# PWR.net
KiCad netlist of a schematic drawn in Altium Designer
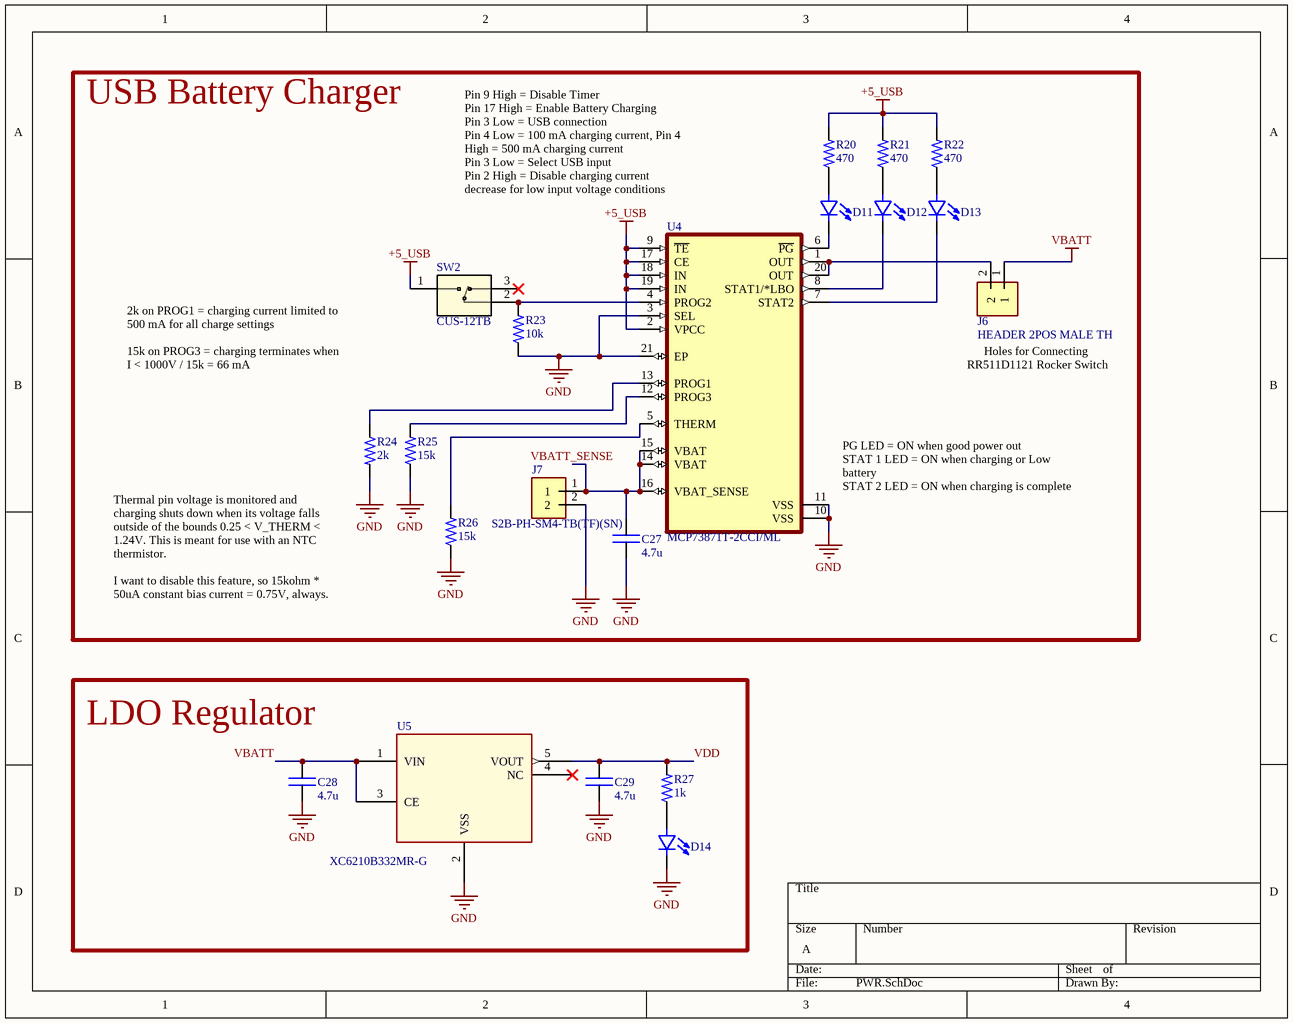
[diagram p0: PWR.SchDoc]

(export (version "E")
  (design (tool "Eeschema 10.0.6"))
  (components
    (comp (ref "C27")
      (value "4.7u")
      (footprint "Christmas-2023_Soundboard:0603-CAP")
      (description "Capaicitor")
      (fields (field (name "Comment") "CAP"))
      (libsource (lib "Christmas-2023_Soundboard") (part "CAP"))
    )
    (comp (ref "C28")
      (value "4.7u")
      (footprint "Christmas-2023_Soundboard:0603-CAP")
      (description "Capaicitor")
      (fields (field (name "Comment") "CAP"))
      (libsource (lib "Christmas-2023_Soundboard") (part "CAP"))
    )
    (comp (ref "C29")
      (value "4.7u")
      (footprint "Christmas-2023_Soundboard:0603-CAP")
      (description "Capaicitor")
      (fields (field (name "Comment") "CAP"))
      (libsource (lib "Christmas-2023_Soundboard") (part "CAP"))
    )
    (comp (ref "D11")
      (value "LED - single")
      (footprint "Christmas-2023_Soundboard:0603-LED")
      (description "LED")
      (fields (field (name "MFR") "MEIHUA"))
      (libsource (lib "Christmas-2023_Soundboard") (part "LED - single"))
    )
    (comp (ref "D12")
      (value "LED - single")
      (footprint "Christmas-2023_Soundboard:0603-LED")
      (description "LED")
      (fields (field (name "MFR") "Hubei KENTO Elec"))
      (libsource (lib "Christmas-2023_Soundboard") (part "LED - single"))
    )
    (comp (ref "D13")
      (value "LED - single")
      (footprint "Christmas-2023_Soundboard:0603-LED")
      (description "LED")
      (fields (field (name "MFR") "Everlight Elec"))
      (libsource (lib "Christmas-2023_Soundboard") (part "LED - single"))
    )
    (comp (ref "D14")
      (value "LED - single")
      (footprint "Christmas-2023_Soundboard:0603-LED")
      (description "LED")
      (fields (field (name "MFR") "Everlight Elec"))
      (libsource (lib "Christmas-2023_Soundboard") (part "LED - single"))
    )
    (comp (ref "J6")
      (value "HEADER 2POS MALE TH")
      (footprint "Christmas-2023_Soundboard:2-pos, 0.1\" TH header")
      (libsource (lib "Christmas-2023_Soundboard") (part "HEADER 2POS MALE TH"))
    )
    (comp (ref "J7")
      (value "S2B-PH-SM4-TB(TF)(SN)")
      (footprint "Christmas-2023_Soundboard:JST_PH-2POS-SMT-RA")
      (description "Connector Header Surface Mount, Right Angle 2 position 0.079 (2.00mm)")
      (fields (field (name "MFR") "JST Sales"))
      (libsource (lib "Christmas-2023_Soundboard") (part "JST CONN 2POS PH"))
    )
    (comp (ref "R20")
      (value "470")
      (footprint "Christmas-2023_Soundboard:0603-RES")
      (description "Resistor")
      (fields (field (name "Comment") "RES"))
      (libsource (lib "Christmas-2023_Soundboard") (part "RES"))
    )
    (comp (ref "R21")
      (value "470")
      (footprint "Christmas-2023_Soundboard:0603-RES")
      (description "Resistor")
      (fields (field (name "Comment") "RES"))
      (libsource (lib "Christmas-2023_Soundboard") (part "RES"))
    )
    (comp (ref "R22")
      (value "470")
      (footprint "Christmas-2023_Soundboard:0603-RES")
      (description "Resistor")
      (fields (field (name "Comment") "RES"))
      (libsource (lib "Christmas-2023_Soundboard") (part "RES"))
    )
    (comp (ref "R23")
      (value "10k")
      (footprint "Christmas-2023_Soundboard:0603-RES")
      (description "Resistor")
      (fields (field (name "Comment") "RES"))
      (libsource (lib "Christmas-2023_Soundboard") (part "RES"))
    )
    (comp (ref "R24")
      (value "2k")
      (footprint "Christmas-2023_Soundboard:0603-RES")
      (description "Resistor")
      (fields (field (name "Comment") "RES"))
      (libsource (lib "Christmas-2023_Soundboard") (part "RES"))
    )
    (comp (ref "R25")
      (value "15k")
      (footprint "Christmas-2023_Soundboard:0603-RES")
      (description "Resistor")
      (fields (field (name "Comment") "RES"))
      (libsource (lib "Christmas-2023_Soundboard") (part "RES"))
    )
    (comp (ref "R26")
      (value "15k")
      (footprint "Christmas-2023_Soundboard:0603-RES")
      (description "Resistor")
      (fields (field (name "Comment") "RES"))
      (libsource (lib "Christmas-2023_Soundboard") (part "RES"))
    )
    (comp (ref "R27")
      (value "1k")
      (footprint "Christmas-2023_Soundboard:0603-RES")
      (description "Resistor")
      (fields (field (name "Comment") "RES"))
      (libsource (lib "Christmas-2023_Soundboard") (part "RES"))
    )
    (comp (ref "SW2")
      (value "CUS-12TB")
      (footprint "Christmas-2023_Soundboard:SSSS811101")
      (description "JLC Alternate:\r\nSSSS811101")
      (fields (field (name "MFR") "ALPSALPINE"))
      (libsource (lib "Christmas-2023_Soundboard") (part "SPDT SLIDE SWITCH"))
    )
    (comp (ref "U4")
      (value "MCP73871T-2CCI/ML")
      (footprint "Christmas-2023_Soundboard:20-VFQFN EXPOSED PAD")
      (description "Charger IC Lithium Ion/Polymer 20-QFN (4x4)")
      (fields (field (name "MFR") "Microchip Technology"))
      (libsource (lib "Christmas-2023_Soundboard") (part "LiPo Batt Charger - Shared load"))
    )
    (comp (ref "U5")
      (value "XC6210B332MR-G")
      (footprint "Christmas-2023_Soundboard:SOT-25-5")
      (description "No Description Available")
      (fields (field (name "MFR") "Torex Semiconductor"))
      (libsource (lib "Christmas-2023_Soundboard") (part "LDO 3.3V FIXED 700mA"))
    )
  )
  (nets
    (net (code "1") (name "+5_USB") (class "Default")
      (node (ref "R20") (pin "2") (pinfunction "2_2") (pintype "passive"))
      (node (ref "R21") (pin "2") (pinfunction "2_2") (pintype "passive"))
      (node (ref "R22") (pin "2") (pinfunction "2_2") (pintype "passive"))
      (node (ref "SW2") (pin "1") (pinfunction "1_1") (pintype "passive"))
      (node (ref "U4") (pin "17") (pinfunction "CE_17") (pintype "input"))
      (node (ref "U4") (pin "18") (pinfunction "IN_18") (pintype "input"))
      (node (ref "U4") (pin "19") (pinfunction "IN_19") (pintype "input"))
      (node (ref "U4") (pin "2") (pinfunction "VPCC_2") (pintype "input"))
      (node (ref "U4") (pin "9") (pinfunction "~{TE}_9") (pintype "input"))
    )
    (net (code "2") (name "/VBATT_SENSE") (class "Default")
      (node (ref "C27") (pin "1") (pinfunction "1_1") (pintype "passive"))
      (node (ref "J7") (pin "1") (pinfunction "1_1") (pintype "passive"))
      (node (ref "U4") (pin "14") (pinfunction "VBAT_14") (pintype "bidirectional"))
      (node (ref "U4") (pin "15") (pinfunction "VBAT_15") (pintype "bidirectional"))
      (node (ref "U4") (pin "16") (pinfunction "VBAT_SENSE_16") (pintype "bidirectional"))
    )
    (net (code "3") (name "/VDD") (class "Default")
      (node (ref "C29") (pin "1") (pinfunction "1_1") (pintype "passive"))
      (node (ref "R27") (pin "2") (pinfunction "2_2") (pintype "passive"))
      (node (ref "U5") (pin "5") (pinfunction "VOUT_5") (pintype "output"))
    )
    (net (code "4") (name "GND") (class "Default")
      (node (ref "C27") (pin "2") (pinfunction "2_2") (pintype "passive"))
      (node (ref "C28") (pin "1") (pinfunction "1_1") (pintype "passive"))
      (node (ref "C29") (pin "2") (pinfunction "2_2") (pintype "passive"))
      (node (ref "D14") (pin "2") (pinfunction "C_2") (pintype "passive"))
      (node (ref "J7") (pin "2") (pinfunction "2_2") (pintype "passive"))
      (node (ref "R23") (pin "1") (pinfunction "1_1") (pintype "passive"))
      (node (ref "R24") (pin "2") (pinfunction "2_2") (pintype "passive"))
      (node (ref "R25") (pin "1") (pinfunction "1_1") (pintype "passive"))
      (node (ref "R26") (pin "1") (pinfunction "1_1") (pintype "passive"))
      (node (ref "U4") (pin "10") (pinfunction "VSS_10") (pintype "power_in"))
      (node (ref "U4") (pin "11") (pinfunction "VSS_11") (pintype "power_in"))
      (node (ref "U4") (pin "21") (pinfunction "EP_21") (pintype "bidirectional"))
      (node (ref "U4") (pin "3") (pinfunction "SEL_3") (pintype "input"))
      (node (ref "U5") (pin "2") (pinfunction "VSS_2") (pintype "power_in"))
    )
    (net (code "5") (name "Net-(D11-A)") (class "Default")
      (node (ref "D11") (pin "1") (pinfunction "A_1") (pintype "passive"))
      (node (ref "R20") (pin "1") (pinfunction "1_1") (pintype "passive"))
    )
    (net (code "6") (name "Net-(D11-C)") (class "Default")
      (node (ref "D11") (pin "2") (pinfunction "C_2") (pintype "passive"))
      (node (ref "U4") (pin "6") (pinfunction "~{PG}_6") (pintype "output"))
    )
    (net (code "7") (name "Net-(D12-A)") (class "Default")
      (node (ref "D12") (pin "1") (pinfunction "A_1") (pintype "passive"))
      (node (ref "R21") (pin "1") (pinfunction "1_1") (pintype "passive"))
    )
    (net (code "8") (name "Net-(D12-C)") (class "Default")
      (node (ref "D12") (pin "2") (pinfunction "C_2") (pintype "passive"))
      (node (ref "U4") (pin "8") (pinfunction "STAT1/*LBO_8") (pintype "output"))
    )
    (net (code "9") (name "Net-(D13-A)") (class "Default")
      (node (ref "D13") (pin "1") (pinfunction "A_1") (pintype "passive"))
      (node (ref "R22") (pin "1") (pinfunction "1_1") (pintype "passive"))
    )
    (net (code "10") (name "Net-(D13-C)") (class "Default")
      (node (ref "D13") (pin "2") (pinfunction "C_2") (pintype "passive"))
      (node (ref "U4") (pin "7") (pinfunction "STAT2_7") (pintype "output"))
    )
    (net (code "11") (name "Net-(D14-A)") (class "Default")
      (node (ref "D14") (pin "1") (pinfunction "A_1") (pintype "passive"))
      (node (ref "R27") (pin "1") (pinfunction "1_1") (pintype "passive"))
    )
    (net (code "12") (name "Net-(J6-Pad2)") (class "Default")
      (node (ref "J6") (pin "2") (pinfunction "2_2") (pintype "passive"))
      (node (ref "U4") (pin "1") (pinfunction "OUT_1") (pintype "output"))
      (node (ref "U4") (pin "20") (pinfunction "OUT_20") (pintype "output"))
    )
    (net (code "13") (name "Net-(U4-PROG1)") (class "Default")
      (node (ref "R24") (pin "1") (pinfunction "1_1") (pintype "passive"))
      (node (ref "U4") (pin "13") (pinfunction "PROG1_13") (pintype "bidirectional"))
    )
    (net (code "14") (name "Net-(U4-PROG2)") (class "Default")
      (node (ref "R23") (pin "2") (pinfunction "2_2") (pintype "passive"))
      (node (ref "SW2") (pin "2") (pinfunction "2_2") (pintype "passive"))
      (node (ref "U4") (pin "4") (pinfunction "PROG2_4") (pintype "input"))
    )
    (net (code "15") (name "Net-(U4-PROG3)") (class "Default")
      (node (ref "R25") (pin "2") (pinfunction "2_2") (pintype "passive"))
      (node (ref "U4") (pin "12") (pinfunction "PROG3_12") (pintype "bidirectional"))
    )
    (net (code "16") (name "Net-(U4-THERM)") (class "Default")
      (node (ref "R26") (pin "2") (pinfunction "2_2") (pintype "passive"))
      (node (ref "U4") (pin "5") (pinfunction "THERM_5") (pintype "bidirectional"))
    )
    (net (code "17") (name "VBATT") (class "Default")
      (node (ref "C28") (pin "2") (pinfunction "2_2") (pintype "passive"))
      (node (ref "J6") (pin "1") (pinfunction "1_1") (pintype "passive"))
      (node (ref "U5") (pin "1") (pinfunction "VIN_1") (pintype "power_in"))
      (node (ref "U5") (pin "3") (pinfunction "CE_3") (pintype "passive"))
    )
    (net (code "18") (name "unconnected-(SW2-Pad3)") (class "Default")
      (node (ref "SW2") (pin "3") (pinfunction "3_3") (pintype "passive+no_connect"))
    )
    (net (code "19") (name "unconnected-(U5-NC-Pad4)") (class "Default")
      (node (ref "U5") (pin "4") (pinfunction "NC_4") (pintype "passive+no_connect"))
    )
  )
)
